# MCU.net
KiCad netlist of a schematic drawn in Altium Designer
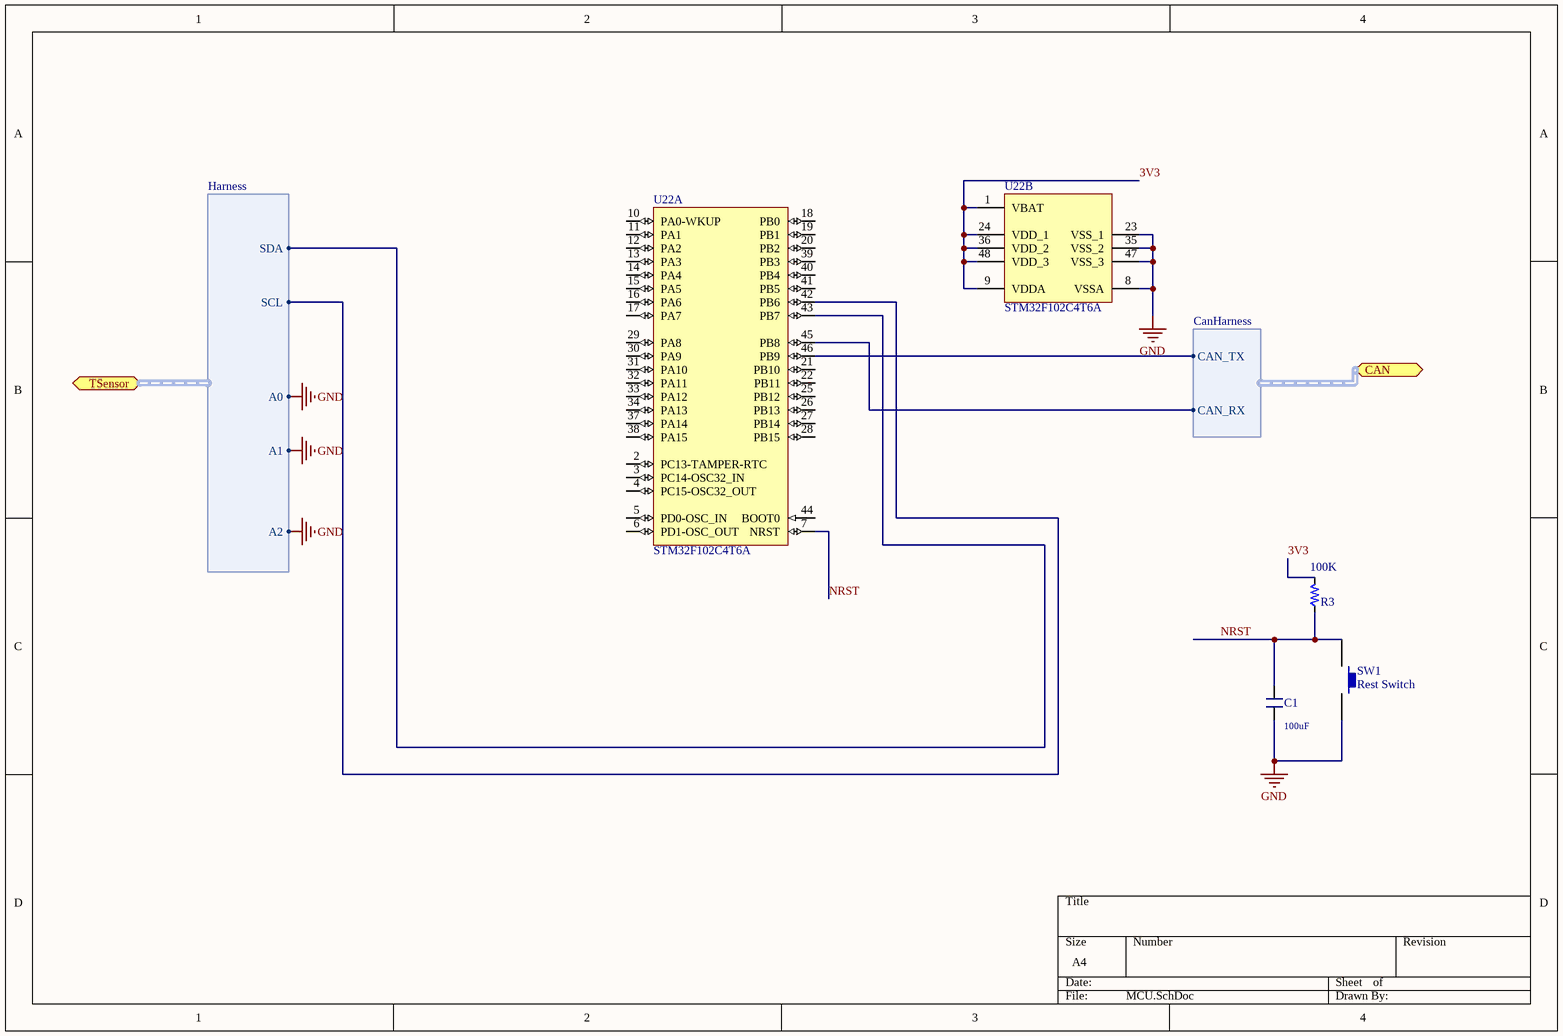
[diagram p0: MCU.SchDoc]

(export (version "E")
  (design (tool "Eeschema 10.0.6"))
  (components
    (comp (ref "C1")
      (value "SCH_GENERIC_CAPACITOR_0603")
      (footprint "PCB_GENERIC_SMD_0603")
      (description "Generic SMD capacitor 0603")
      (fields (field (name "TOLERANCE") "*%") (field (name "CAPACITANCE") "100uF"))
      (libsource (lib "Generic 0603 Capacitor") (part "SCH_GENERIC_CAPACITOR_0603"))
    )
    (comp (ref "R3")
      (value "SCH_GENERIC_RESISTOR_0603")
      (footprint "PCB_GENERIC_SMD_0603")
      (description "Generic SMD resistor 0603")
      (fields (field (name "RESISTANCE") "100K"))
      (libsource (lib "Generic 0603 Resistor") (part "SCH_GENERIC_RESISTOR_0603"))
    )
    (comp (ref "SW1")
      (value "Rest Switch")
      (footprint "Push Button Switch")
      (libsource (lib "Surface Mount Push Button Switch") (part "PushButtonSwitch"))
    )
    (comp (ref "U22")
      (value "STM32F102C4T6A")
      (footprint "STM-LQFP48_N")
      (libsource (lib "STMicroelectronics STM32 F1") (part "STM32F102C4T6A"))
    )
  )
  (nets
    (net (code "3") (name "/3V3") (class "Default")
      (node (ref "R3") (pin "2") (pinfunction "2_2") (pintype "passive"))
      (node (ref "U22") (pin "1") (pinfunction "VBAT_1") (pintype "power_in"))
      (node (ref "U22") (pin "24") (pinfunction "VDD_1_24") (pintype "power_in"))
      (node (ref "U22") (pin "36") (pinfunction "VDD_2_36") (pintype "power_in"))
      (node (ref "U22") (pin "48") (pinfunction "VDD_3_48") (pintype "power_in"))
      (node (ref "U22") (pin "9") (pinfunction "VDDA_9") (pintype "power_in"))
    )
    (net (code "4") (name "/CAN_RX") (class "Default")
      (node (ref "U22") (pin "45") (pinfunction "PB8_45") (pintype "bidirectional"))
    )
    (net (code "5") (name "/CAN_TX") (class "Default")
      (node (ref "U22") (pin "46") (pinfunction "PB9_46") (pintype "bidirectional"))
    )
    (net (code "6") (name "/NRST") (class "Default")
      (node (ref "C1") (pin "2") (pinfunction "2_2") (pintype "passive"))
      (node (ref "R3") (pin "1") (pinfunction "1_1") (pintype "passive"))
      (node (ref "SW1") (pin "1") (pinfunction "1_1") (pintype "passive"))
      (node (ref "U22") (pin "7") (pinfunction "NRST_7") (pintype "bidirectional"))
    )
    (net (code "7") (name "/SCL") (class "Default")
      (node (ref "U22") (pin "42") (pinfunction "PB6_42") (pintype "bidirectional"))
    )
    (net (code "8") (name "/SDA") (class "Default")
      (node (ref "U22") (pin "43") (pinfunction "PB7_43") (pintype "bidirectional"))
    )
    (net (code "11") (name "GND") (class "Default")
      (node (ref "C1") (pin "1") (pinfunction "1_1") (pintype "passive"))
      (node (ref "SW1") (pin "2") (pinfunction "2_2") (pintype "passive"))
      (node (ref "U22") (pin "23") (pinfunction "VSS_1_23") (pintype "power_in"))
      (node (ref "U22") (pin "35") (pinfunction "VSS_2_35") (pintype "power_in"))
      (node (ref "U22") (pin "47") (pinfunction "VSS_3_47") (pintype "power_in"))
      (node (ref "U22") (pin "8") (pinfunction "VSSA_8") (pintype "power_in"))
    )
    (net (code "12") (name "unconnected-(U22A-BOOT0-Pad44)") (class "Default")
      (node (ref "U22") (pin "44") (pinfunction "BOOT0_44") (pintype "input"))
    )
    (net (code "13") (name "unconnected-(U22A-PA0-WKUP-Pad10)") (class "Default")
      (node (ref "U22") (pin "10") (pinfunction "PA0-WKUP_10") (pintype "bidirectional"))
    )
    (net (code "14") (name "unconnected-(U22A-PA1-Pad11)") (class "Default")
      (node (ref "U22") (pin "11") (pinfunction "PA1_11") (pintype "bidirectional"))
    )
    (net (code "15") (name "unconnected-(U22A-PA2-Pad12)") (class "Default")
      (node (ref "U22") (pin "12") (pinfunction "PA2_12") (pintype "bidirectional"))
    )
    (net (code "16") (name "unconnected-(U22A-PA3-Pad13)") (class "Default")
      (node (ref "U22") (pin "13") (pinfunction "PA3_13") (pintype "bidirectional"))
    )
    (net (code "17") (name "unconnected-(U22A-PA4-Pad14)") (class "Default")
      (node (ref "U22") (pin "14") (pinfunction "PA4_14") (pintype "bidirectional"))
    )
    (net (code "18") (name "unconnected-(U22A-PA5-Pad15)") (class "Default")
      (node (ref "U22") (pin "15") (pinfunction "PA5_15") (pintype "bidirectional"))
    )
    (net (code "19") (name "unconnected-(U22A-PA6-Pad16)") (class "Default")
      (node (ref "U22") (pin "16") (pinfunction "PA6_16") (pintype "bidirectional"))
    )
    (net (code "20") (name "unconnected-(U22A-PA7-Pad17)") (class "Default")
      (node (ref "U22") (pin "17") (pinfunction "PA7_17") (pintype "bidirectional"))
    )
    (net (code "21") (name "unconnected-(U22A-PA8-Pad29)") (class "Default")
      (node (ref "U22") (pin "29") (pinfunction "PA8_29") (pintype "bidirectional"))
    )
    (net (code "22") (name "unconnected-(U22A-PA9-Pad30)") (class "Default")
      (node (ref "U22") (pin "30") (pinfunction "PA9_30") (pintype "bidirectional"))
    )
    (net (code "23") (name "unconnected-(U22A-PA10-Pad31)") (class "Default")
      (node (ref "U22") (pin "31") (pinfunction "PA10_31") (pintype "bidirectional"))
    )
    (net (code "24") (name "unconnected-(U22A-PA11-Pad32)") (class "Default")
      (node (ref "U22") (pin "32") (pinfunction "PA11_32") (pintype "bidirectional"))
    )
    (net (code "25") (name "unconnected-(U22A-PA12-Pad33)") (class "Default")
      (node (ref "U22") (pin "33") (pinfunction "PA12_33") (pintype "bidirectional"))
    )
    (net (code "26") (name "unconnected-(U22A-PA13-Pad34)") (class "Default")
      (node (ref "U22") (pin "34") (pinfunction "PA13_34") (pintype "bidirectional"))
    )
    (net (code "27") (name "unconnected-(U22A-PA14-Pad37)") (class "Default")
      (node (ref "U22") (pin "37") (pinfunction "PA14_37") (pintype "bidirectional"))
    )
    (net (code "28") (name "unconnected-(U22A-PA15-Pad38)") (class "Default")
      (node (ref "U22") (pin "38") (pinfunction "PA15_38") (pintype "bidirectional"))
    )
    (net (code "29") (name "unconnected-(U22A-PB0-Pad18)") (class "Default")
      (node (ref "U22") (pin "18") (pinfunction "PB0_18") (pintype "bidirectional"))
    )
    (net (code "30") (name "unconnected-(U22A-PB1-Pad19)") (class "Default")
      (node (ref "U22") (pin "19") (pinfunction "PB1_19") (pintype "bidirectional"))
    )
    (net (code "31") (name "unconnected-(U22A-PB2-Pad20)") (class "Default")
      (node (ref "U22") (pin "20") (pinfunction "PB2_20") (pintype "bidirectional"))
    )
    (net (code "32") (name "unconnected-(U22A-PB3-Pad39)") (class "Default")
      (node (ref "U22") (pin "39") (pinfunction "PB3_39") (pintype "bidirectional"))
    )
    (net (code "33") (name "unconnected-(U22A-PB4-Pad40)") (class "Default")
      (node (ref "U22") (pin "40") (pinfunction "PB4_40") (pintype "bidirectional"))
    )
    (net (code "34") (name "unconnected-(U22A-PB5-Pad41)") (class "Default")
      (node (ref "U22") (pin "41") (pinfunction "PB5_41") (pintype "bidirectional"))
    )
    (net (code "35") (name "unconnected-(U22A-PB10-Pad21)") (class "Default")
      (node (ref "U22") (pin "21") (pinfunction "PB10_21") (pintype "bidirectional"))
    )
    (net (code "36") (name "unconnected-(U22A-PB11-Pad22)") (class "Default")
      (node (ref "U22") (pin "22") (pinfunction "PB11_22") (pintype "bidirectional"))
    )
    (net (code "37") (name "unconnected-(U22A-PB12-Pad25)") (class "Default")
      (node (ref "U22") (pin "25") (pinfunction "PB12_25") (pintype "bidirectional"))
    )
    (net (code "38") (name "unconnected-(U22A-PB13-Pad26)") (class "Default")
      (node (ref "U22") (pin "26") (pinfunction "PB13_26") (pintype "bidirectional"))
    )
    (net (code "39") (name "unconnected-(U22A-PB14-Pad27)") (class "Default")
      (node (ref "U22") (pin "27") (pinfunction "PB14_27") (pintype "bidirectional"))
    )
    (net (code "40") (name "unconnected-(U22A-PB15-Pad28)") (class "Default")
      (node (ref "U22") (pin "28") (pinfunction "PB15_28") (pintype "bidirectional"))
    )
    (net (code "41") (name "unconnected-(U22A-PC13-TAMPER-RTC-Pad2)") (class "Default")
      (node (ref "U22") (pin "2") (pinfunction "PC13-TAMPER-RTC_2") (pintype "bidirectional"))
    )
    (net (code "42") (name "unconnected-(U22A-PC14-OSC32_IN-Pad3)") (class "Default")
      (node (ref "U22") (pin "3") (pinfunction "PC14-OSC32_IN_3") (pintype "bidirectional"))
    )
    (net (code "43") (name "unconnected-(U22A-PC15-OSC32_OUT-Pad4)") (class "Default")
      (node (ref "U22") (pin "4") (pinfunction "PC15-OSC32_OUT_4") (pintype "bidirectional"))
    )
    (net (code "44") (name "unconnected-(U22A-PD0-OSC_IN-Pad5)") (class "Default")
      (node (ref "U22") (pin "5") (pinfunction "PD0-OSC_IN_5") (pintype "bidirectional"))
    )
    (net (code "45") (name "unconnected-(U22A-PD1-OSC_OUT-Pad6)") (class "Default")
      (node (ref "U22") (pin "6") (pinfunction "PD1-OSC_OUT_6") (pintype "bidirectional"))
    )
  )
)
